# Impedance.net
KiCad netlist of a schematic drawn in EAGLE
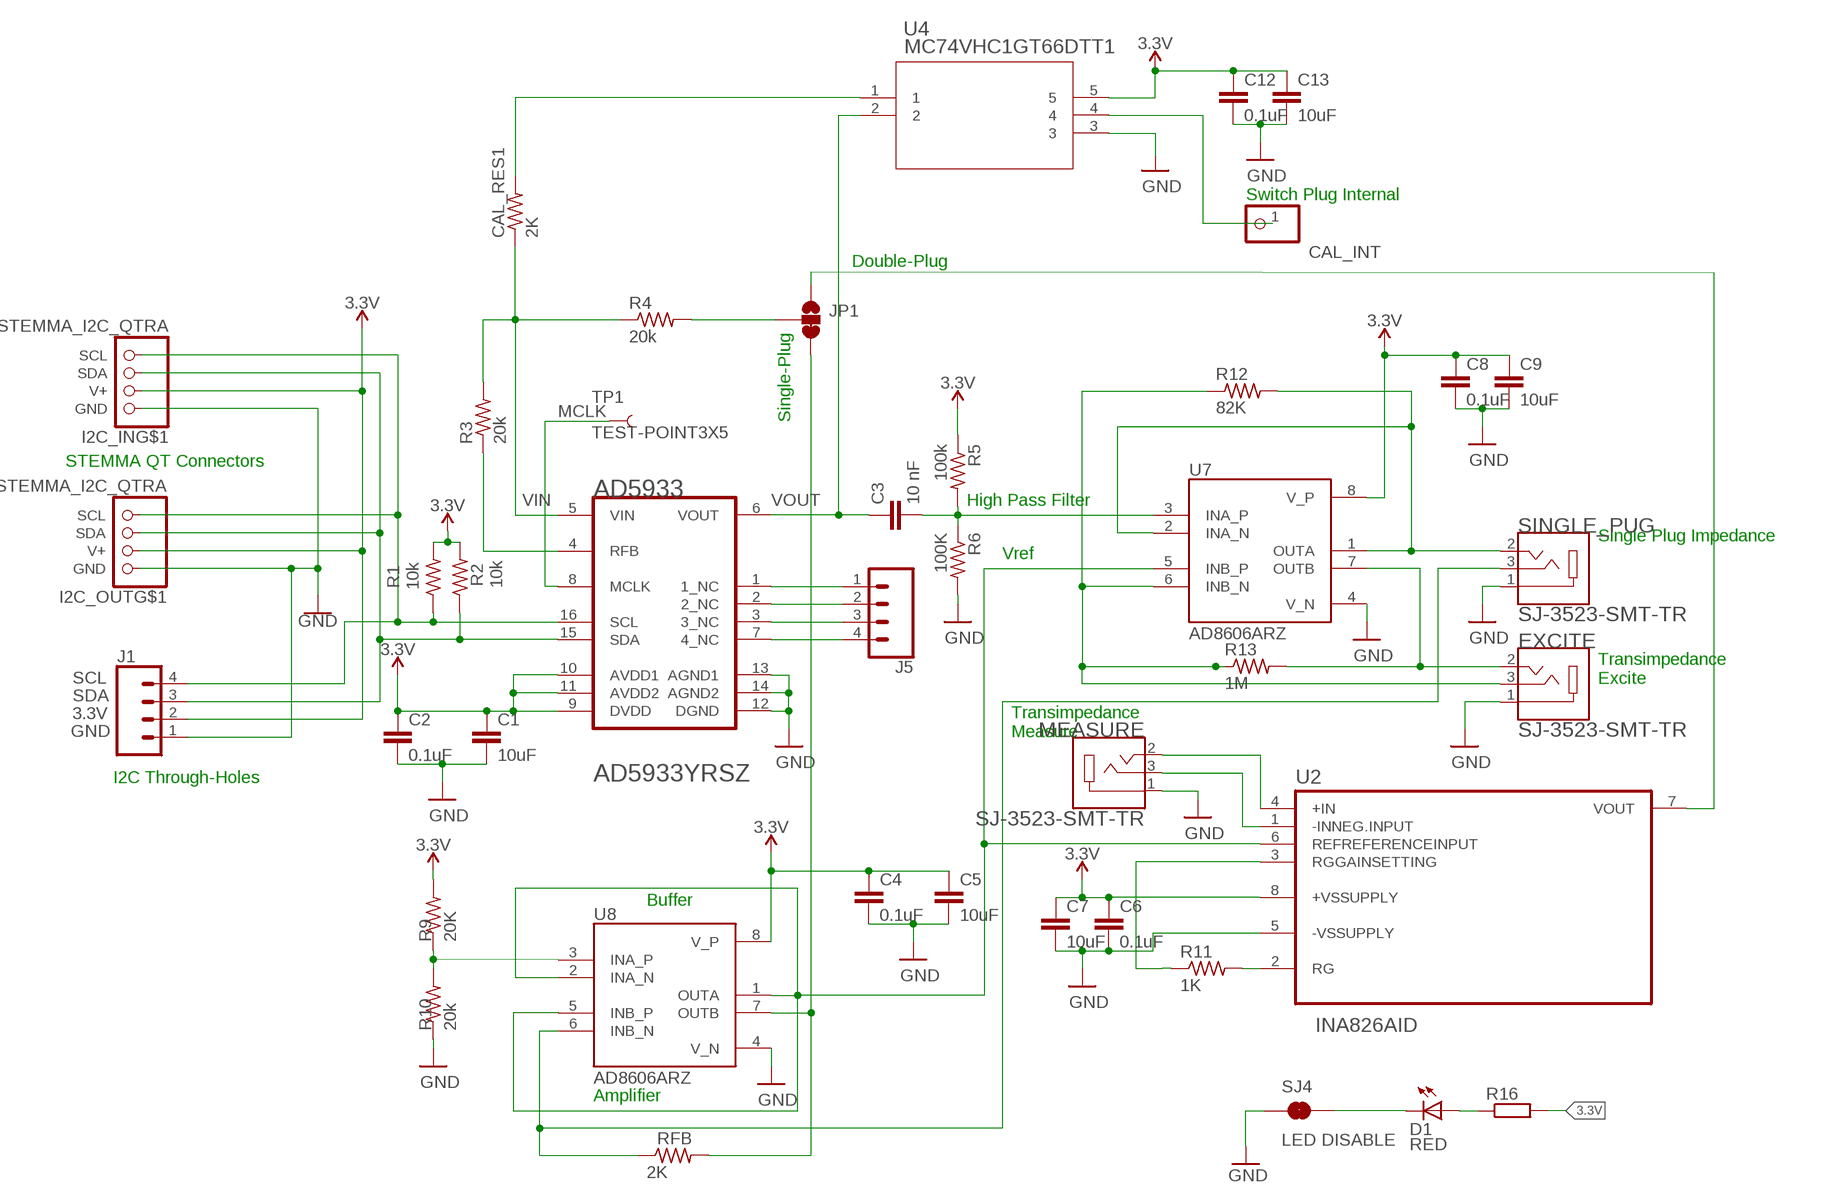
[diagram p0: schematic, sheet 1]

(export (version "E")
  (design (tool "Eeschema 10.0.6"))
  (components
    (comp (ref "AD5933")
      (value "ANALOG_DEVICES_AD5933YRSZANALOG_DEVICES_AD5933YRSZ_0_0")
      (footprint "eagle-import:ANALOG_DEVICES_AD5933YRSZ_0")
      (fields (field (name "MF") "Analog Devices") (field (name "MPN") "AD5933YRSZ"))
      (libsource (lib "eagle-import") (part "ANALOG_DEVICES_AD5933YRSZANALOG_DEVICES_AD5933YRSZ_0_0"))
    )
    (comp (ref "C1")
      (value "10uF")
      (footprint "eagle-import:C0603")
      (libsource (lib "eagle-import") (part "C-EUC0603"))
    )
    (comp (ref "C2")
      (value "0.1uF")
      (footprint "eagle-import:C0603")
      (libsource (lib "eagle-import") (part "C-EUC0603"))
    )
    (comp (ref "C3")
      (value "10 nF")
      (footprint "eagle-import:C0603")
      (libsource (lib "eagle-import") (part "C-EUC0603"))
    )
    (comp (ref "C4")
      (value "0.1uF")
      (footprint "eagle-import:C0603")
      (libsource (lib "eagle-import") (part "C-EUC0603"))
    )
    (comp (ref "C5")
      (value "10uF")
      (footprint "eagle-import:C0603")
      (libsource (lib "eagle-import") (part "C-EUC0603"))
    )
    (comp (ref "C6")
      (value "0.1uF")
      (footprint "eagle-import:C0603")
      (libsource (lib "eagle-import") (part "C-EUC0603"))
    )
    (comp (ref "C7")
      (value "10uF")
      (footprint "eagle-import:C0603")
      (libsource (lib "eagle-import") (part "C-EUC0603"))
    )
    (comp (ref "C8")
      (value "0.1uF")
      (footprint "eagle-import:C0603")
      (libsource (lib "eagle-import") (part "C-EUC0603"))
    )
    (comp (ref "C9")
      (value "10uF")
      (footprint "eagle-import:C0603")
      (libsource (lib "eagle-import") (part "C-EUC0603"))
    )
    (comp (ref "C12")
      (value "0.1uF")
      (footprint "eagle-import:C0603")
      (libsource (lib "eagle-import") (part "C-EUC0603"))
    )
    (comp (ref "C13")
      (value "10uF")
      (footprint "eagle-import:C0603")
      (libsource (lib "eagle-import") (part "C-EUC0603"))
    )
    (comp (ref "CAL_INT")
      (value "PINHD-1X1")
      (footprint "eagle-import:1X01")
      (libsource (lib "eagle-import") (part "PINHD-1X1"))
    )
    (comp (ref "CAL_RES1")
      (value "2K")
      (footprint "eagle-import:R0603")
      (libsource (lib "eagle-import") (part "R-US_R0603"))
    )
    (comp (ref "D1")
      (value "RED")
      (footprint "eagle-import:LED-0603")
      (libsource (lib "eagle-import") (part "LED-RED0603"))
    )
    (comp (ref "EXCITE")
      (value "SJ-3523-SMT-TR")
      (footprint "eagle-import:CUI_SJ-3523-SMT-TR")
      (fields (field (name "MF") "CUI Devices"))
      (libsource (lib "eagle-import") (part "SJ-3523-SMT-TR"))
    )
    (comp (ref "I2C_IN")
      (value "STEMMA_I2C_QTRA")
      (footprint "eagle-import:JST_SH4_RA")
      (libsource (lib "eagle-import") (part "STEMMA_I2C_QTRA"))
    )
    (comp (ref "I2C_OUT")
      (value "STEMMA_I2C_QTRA")
      (footprint "eagle-import:JST_SH4_RA")
      (libsource (lib "eagle-import") (part "STEMMA_I2C_QTRA"))
    )
    (comp (ref "J1")
      (value "CONN_04")
      (footprint "eagle-import:1X04")
      (libsource (lib "eagle-import") (part "CONN_04"))
    )
    (comp (ref "J5")
      (value "CONN_04")
      (footprint "eagle-import:1X04")
      (libsource (lib "eagle-import") (part "CONN_04"))
    )
    (comp (ref "JP1")
      (value "JUMPER-SMT_3_1-NC_TRACE_NO-SILK")
      (footprint "eagle-import:SMT-JUMPER_3_1-NC_TRACE_NO-SILK")
      (libsource (lib "eagle-import") (part "JUMPER-SMT_3_1-NC_TRACE_NO-SILK"))
    )
    (comp (ref "MEASURE")
      (value "SJ-3523-SMT-TR")
      (footprint "eagle-import:CUI_SJ-3523-SMT-TR")
      (fields (field (name "MF") "CUI Devices"))
      (libsource (lib "eagle-import") (part "SJ-3523-SMT-TR"))
    )
    (comp (ref "R1")
      (value "10k")
      (footprint "eagle-import:R0603")
      (libsource (lib "eagle-import") (part "R-US_R0603"))
    )
    (comp (ref "R2")
      (value "10k")
      (footprint "eagle-import:R0603")
      (libsource (lib "eagle-import") (part "R-US_R0603"))
    )
    (comp (ref "R3")
      (value "20k")
      (footprint "eagle-import:R0603")
      (libsource (lib "eagle-import") (part "R-US_R0603"))
    )
    (comp (ref "R4")
      (value "20k")
      (footprint "eagle-import:R0603")
      (libsource (lib "eagle-import") (part "R-US_R0603"))
    )
    (comp (ref "R5")
      (value "100k")
      (footprint "eagle-import:R0603")
      (libsource (lib "eagle-import") (part "R-US_R0603"))
    )
    (comp (ref "R6")
      (value "100K")
      (footprint "eagle-import:R0603")
      (libsource (lib "eagle-import") (part "R-US_R0603"))
    )
    (comp (ref "R9")
      (value "20K")
      (footprint "eagle-import:R0603")
      (libsource (lib "eagle-import") (part "R-US_R0603"))
    )
    (comp (ref "R10")
      (value "20k")
      (footprint "eagle-import:R0603")
      (libsource (lib "eagle-import") (part "R-US_R0603"))
    )
    (comp (ref "R11")
      (value "1K")
      (footprint "eagle-import:R0603")
      (libsource (lib "eagle-import") (part "R-US_R0603"))
    )
    (comp (ref "R12")
      (value "82K")
      (footprint "eagle-import:R0603")
      (libsource (lib "eagle-import") (part "R-US_R0603"))
    )
    (comp (ref "R13")
      (value "1M")
      (footprint "eagle-import:R0603")
      (libsource (lib "eagle-import") (part "R-US_R0603"))
    )
    (comp (ref "R16")
      (value "R__0603")
      (footprint "eagle-import:R0603")
      (fields (field (name "LCSC_PART") "C21190"))
      (libsource (lib "eagle-import") (part "R__06031K"))
    )
    (comp (ref "RFB")
      (value "2K")
      (footprint "eagle-import:R0603")
      (libsource (lib "eagle-import") (part "R-US_R0603"))
    )
    (comp (ref "SINGLE_PUG")
      (value "SJ-3523-SMT-TR")
      (footprint "eagle-import:CUI_SJ-3523-SMT-TR")
      (fields (field (name "MF") "CUI Devices"))
      (libsource (lib "eagle-import") (part "SJ-3523-SMT-TR"))
    )
    (comp (ref "SJ4")
      (value "LED DISABLE")
      (footprint "eagle-import:SMT-JUMPER_2_NC_TRACE_NO-SILK")
      (libsource (lib "eagle-import") (part "JUMPER-SMT_2_NC_TRACE_NO-SILK"))
    )
    (comp (ref "TP1")
      (value "TEST-POINT3X5")
      (footprint "eagle-import:PAD.03X.05")
      (libsource (lib "eagle-import") (part "TEST-POINT3X5"))
    )
    (comp (ref "U2")
      (value "INA826AID")
      (footprint "eagle-import:SOIC127P599X175-8N")
      (fields (field (name "MF") "Texas Instruments"))
      (libsource (lib "eagle-import") (part "INA826AID"))
    )
    (comp (ref "U4")
      (value "MC74VHC1GT66DTT1")
      (footprint "eagle-import:TSOP5_1P65X3P15_ONS")
      (fields (field (name "COPYRIGHT") "Copyright (C) 2024 Ultra Librarian. All rights reserved."))
      (libsource (lib "eagle-import") (part "MC74VHC1GT66DTT1"))
    )
    (comp (ref "U7")
      (value "AD8606ARZ")
      (footprint "eagle-import:SOIC127P600X175-8N")
      (fields (field (name "MF") "Analog Devices"))
      (libsource (lib "eagle-import") (part "AD8606ARZ"))
    )
    (comp (ref "U8")
      (value "AD8606ARZ")
      (footprint "eagle-import:SOIC127P600X175-8N")
      (fields (field (name "MF") "Analog Devices"))
      (libsource (lib "eagle-import") (part "AD8606ARZ"))
    )
  )
  (nets
    (net (code "1") (name "/MCLK") (class "Default")
      (node (ref "AD5933") (pin "8") (pinfunction "MCLK_8") (pintype "input"))
      (node (ref "TP1") (pin "P$1") (pinfunction "1_P$1") (pintype "bidirectional"))
    )
    (net (code "2") (name "/SCL") (class "Default")
      (node (ref "AD5933") (pin "16") (pinfunction "SCL_16") (pintype "input"))
      (node (ref "I2C_IN") (pin "4") (pinfunction "SCL_4") (pintype "passive"))
      (node (ref "I2C_OUT") (pin "4") (pinfunction "SCL_4") (pintype "passive"))
      (node (ref "J1") (pin "4") (pinfunction "4_4") (pintype "passive"))
      (node (ref "R1") (pin "1") (pinfunction "1_1") (pintype "passive"))
    )
    (net (code "3") (name "/SDA") (class "Default")
      (node (ref "AD5933") (pin "15") (pinfunction "SDA_15") (pintype "bidirectional"))
      (node (ref "I2C_IN") (pin "3") (pinfunction "SDA_3") (pintype "passive"))
      (node (ref "I2C_OUT") (pin "3") (pinfunction "SDA_3") (pintype "passive"))
      (node (ref "J1") (pin "3") (pinfunction "3_3") (pintype "passive"))
      (node (ref "R2") (pin "1") (pinfunction "1_1") (pintype "passive"))
    )
    (net (code "4") (name "/VIN") (class "Default")
      (node (ref "AD5933") (pin "5") (pinfunction "VIN_5") (pintype "input"))
      (node (ref "CAL_RES1") (pin "1") (pinfunction "1_1") (pintype "passive"))
      (node (ref "R3") (pin "2") (pinfunction "2_2") (pintype "passive"))
      (node (ref "R4") (pin "1") (pinfunction "1_1") (pintype "passive"))
    )
    (net (code "5") (name "/VOUT") (class "Default")
      (node (ref "AD5933") (pin "6") (pinfunction "VOUT_6") (pintype "output"))
      (node (ref "C3") (pin "1") (pinfunction "1_1") (pintype "passive"))
      (node (ref "U4") (pin "2") (pinfunction "2_2") (pintype "passive"))
    )
    (net (code "6") (name "3.3V") (class "Default")
      (node (ref "AD5933") (pin "10") (pinfunction "AVDD1_10") (pintype "power_in"))
      (node (ref "AD5933") (pin "11") (pinfunction "AVDD2_11") (pintype "power_in"))
      (node (ref "AD5933") (pin "9") (pinfunction "DVDD_9") (pintype "power_in"))
      (node (ref "C1") (pin "1") (pinfunction "1_1") (pintype "passive"))
      (node (ref "C12") (pin "1") (pinfunction "1_1") (pintype "passive"))
      (node (ref "C13") (pin "1") (pinfunction "1_1") (pintype "passive"))
      (node (ref "C2") (pin "1") (pinfunction "1_1") (pintype "passive"))
      (node (ref "C4") (pin "1") (pinfunction "1_1") (pintype "passive"))
      (node (ref "C5") (pin "1") (pinfunction "1_1") (pintype "passive"))
      (node (ref "C6") (pin "1") (pinfunction "1_1") (pintype "passive"))
      (node (ref "C7") (pin "1") (pinfunction "1_1") (pintype "passive"))
      (node (ref "C8") (pin "1") (pinfunction "1_1") (pintype "passive"))
      (node (ref "C9") (pin "1") (pinfunction "1_1") (pintype "passive"))
      (node (ref "I2C_IN") (pin "2") (pinfunction "V+_2") (pintype "passive"))
      (node (ref "I2C_OUT") (pin "2") (pinfunction "V+_2") (pintype "passive"))
      (node (ref "J1") (pin "2") (pinfunction "2_2") (pintype "passive"))
      (node (ref "R1") (pin "2") (pinfunction "2_2") (pintype "passive"))
      (node (ref "R16") (pin "2") (pinfunction "2_2") (pintype "passive"))
      (node (ref "R2") (pin "2") (pinfunction "2_2") (pintype "passive"))
      (node (ref "R5") (pin "1") (pinfunction "1_1") (pintype "passive"))
      (node (ref "R9") (pin "2") (pinfunction "2_2") (pintype "passive"))
      (node (ref "U2") (pin "8") (pinfunction "+VSSUPPLY_8") (pintype "bidirectional"))
      (node (ref "U4") (pin "5") (pinfunction "5_5") (pintype "passive"))
      (node (ref "U7") (pin "8") (pinfunction "V_P_8") (pintype "power_in"))
      (node (ref "U8") (pin "8") (pinfunction "V_P_8") (pintype "power_in"))
    )
    (net (code "7") (name "GND") (class "Default")
      (node (ref "AD5933") (pin "12") (pinfunction "DGND_12") (pintype "power_in"))
      (node (ref "AD5933") (pin "13") (pinfunction "AGND1_13") (pintype "power_in"))
      (node (ref "AD5933") (pin "14") (pinfunction "AGND2_14") (pintype "power_in"))
      (node (ref "C1") (pin "2") (pinfunction "2_2") (pintype "passive"))
      (node (ref "C12") (pin "2") (pinfunction "2_2") (pintype "passive"))
      (node (ref "C13") (pin "2") (pinfunction "2_2") (pintype "passive"))
      (node (ref "C2") (pin "2") (pinfunction "2_2") (pintype "passive"))
      (node (ref "C4") (pin "2") (pinfunction "2_2") (pintype "passive"))
      (node (ref "C5") (pin "2") (pinfunction "2_2") (pintype "passive"))
      (node (ref "C6") (pin "2") (pinfunction "2_2") (pintype "passive"))
      (node (ref "C7") (pin "2") (pinfunction "2_2") (pintype "passive"))
      (node (ref "C8") (pin "2") (pinfunction "2_2") (pintype "passive"))
      (node (ref "C9") (pin "2") (pinfunction "2_2") (pintype "passive"))
      (node (ref "EXCITE") (pin "1") (pinfunction "1_1") (pintype "passive"))
      (node (ref "I2C_IN") (pin "1") (pinfunction "GND_1") (pintype "passive"))
      (node (ref "I2C_OUT") (pin "1") (pinfunction "GND_1") (pintype "passive"))
      (node (ref "J1") (pin "1") (pinfunction "1_1") (pintype "passive"))
      (node (ref "MEASURE") (pin "1") (pinfunction "1_1") (pintype "passive"))
      (node (ref "R10") (pin "1") (pinfunction "1_1") (pintype "passive"))
      (node (ref "R6") (pin "2") (pinfunction "2_2") (pintype "passive"))
      (node (ref "SINGLE_PUG") (pin "1") (pinfunction "1_1") (pintype "passive"))
      (node (ref "SJ4") (pin "1") (pinfunction "1_1") (pintype "passive"))
      (node (ref "U2") (pin "5") (pinfunction "-VSSUPPLY_5") (pintype "bidirectional"))
      (node (ref "U4") (pin "3") (pinfunction "3_3") (pintype "passive"))
      (node (ref "U7") (pin "4") (pinfunction "V_N_4") (pintype "power_in"))
      (node (ref "U8") (pin "4") (pinfunction "V_N_4") (pintype "power_in"))
    )
    (net (code "8") (name "Net-(AD5933-1_NC)") (class "Default")
      (node (ref "AD5933") (pin "1") (pinfunction "1_NC_1") (pintype "passive"))
      (node (ref "J5") (pin "1") (pinfunction "1_1") (pintype "passive"))
    )
    (net (code "9") (name "Net-(AD5933-2_NC)") (class "Default")
      (node (ref "AD5933") (pin "2") (pinfunction "2_NC_2") (pintype "passive"))
      (node (ref "J5") (pin "2") (pinfunction "2_2") (pintype "passive"))
    )
    (net (code "10") (name "Net-(AD5933-3_NC)") (class "Default")
      (node (ref "AD5933") (pin "3") (pinfunction "3_NC_3") (pintype "passive"))
      (node (ref "J5") (pin "3") (pinfunction "3_3") (pintype "passive"))
    )
    (net (code "11") (name "Net-(AD5933-4_NC)") (class "Default")
      (node (ref "AD5933") (pin "7") (pinfunction "4_NC_7") (pintype "passive"))
      (node (ref "J5") (pin "4") (pinfunction "4_4") (pintype "passive"))
    )
    (net (code "12") (name "Net-(AD5933-RFB)") (class "Default")
      (node (ref "AD5933") (pin "4") (pinfunction "RFB_4") (pintype "input"))
      (node (ref "R3") (pin "1") (pinfunction "1_1") (pintype "passive"))
    )
    (net (code "13") (name "Net-(CAL_INT-Pad1)") (class "Default")
      (node (ref "CAL_INT") (pin "1") (pinfunction "1_1") (pintype "passive"))
      (node (ref "U4") (pin "4") (pinfunction "4_4") (pintype "passive"))
    )
    (net (code "14") (name "Net-(CAL_RES1-Pad2)") (class "Default")
      (node (ref "CAL_RES1") (pin "2") (pinfunction "2_2") (pintype "passive"))
      (node (ref "U4") (pin "1") (pinfunction "1_1") (pintype "passive"))
    )
    (net (code "15") (name "Net-(D1-PadA)") (class "Default")
      (node (ref "D1") (pin "A") (pinfunction "A_A") (pintype "passive"))
      (node (ref "R16") (pin "1") (pinfunction "1_1") (pintype "passive"))
    )
    (net (code "16") (name "Net-(D1-PadC)") (class "Default")
      (node (ref "D1") (pin "C") (pinfunction "C_C") (pintype "passive"))
      (node (ref "SJ4") (pin "2") (pinfunction "2_2") (pintype "passive"))
    )
    (net (code "17") (name "Net-(JP1-Pad2)") (class "Default")
      (node (ref "JP1") (pin "2") (pinfunction "2_2") (pintype "passive"))
      (node (ref "R4") (pin "2") (pinfunction "2_2") (pintype "passive"))
    )
    (net (code "18") (name "Net-(U2-+IN)") (class "Default")
      (node (ref "MEASURE") (pin "2") (pinfunction "2_2") (pintype "passive"))
      (node (ref "U2") (pin "4") (pinfunction "+IN_4") (pintype "input"))
    )
    (net (code "19") (name "Net-(U2--INNEG.INPUT)") (class "Default")
      (node (ref "MEASURE") (pin "3") (pinfunction "3_3") (pintype "passive"))
      (node (ref "U2") (pin "1") (pinfunction "-INNEG.INPUT_1") (pintype "input"))
    )
    (net (code "20") (name "Net-(U2-REFREFERENCEINPUT)") (class "Default")
      (node (ref "U2") (pin "6") (pinfunction "REFREFERENCEINPUT_6") (pintype "input"))
      (node (ref "U7") (pin "5") (pinfunction "INB_P_5") (pintype "input"))
      (node (ref "U8") (pin "1") (pinfunction "OUTA_1") (pintype "input"))
      (node (ref "U8") (pin "2") (pinfunction "INA_N_2") (pintype "input"))
      (node (ref "U8") (pin "5") (pinfunction "INB_P_5") (pintype "input"))
    )
    (net (code "21") (name "Net-(U2-RG)") (class "Default")
      (node (ref "R11") (pin "2") (pinfunction "2_2") (pintype "passive"))
      (node (ref "U2") (pin "2") (pinfunction "RG_2") (pintype "bidirectional"))
    )
    (net (code "22") (name "Net-(U2-RGGAINSETTING)") (class "Default")
      (node (ref "R11") (pin "1") (pinfunction "1_1") (pintype "passive"))
      (node (ref "U2") (pin "3") (pinfunction "RGGAINSETTING_3") (pintype "input"))
    )
    (net (code "23") (name "Net-(U2-VOUT)") (class "Default")
      (node (ref "JP1") (pin "1") (pinfunction "1_1") (pintype "passive"))
      (node (ref "U2") (pin "7") (pinfunction "VOUT_7") (pintype "output"))
    )
    (net (code "24") (name "Net-(U7-INA_N)") (class "Default")
      (node (ref "R12") (pin "2") (pinfunction "2_2") (pintype "passive"))
      (node (ref "SINGLE_PUG") (pin "2") (pinfunction "2_2") (pintype "passive"))
      (node (ref "U7") (pin "1") (pinfunction "OUTA_1") (pintype "input"))
      (node (ref "U7") (pin "2") (pinfunction "INA_N_2") (pintype "input"))
    )
    (net (code "25") (name "Net-(U7-INA_P)") (class "Default")
      (node (ref "C3") (pin "2") (pinfunction "2_2") (pintype "passive"))
      (node (ref "R5") (pin "2") (pinfunction "2_2") (pintype "passive"))
      (node (ref "R6") (pin "1") (pinfunction "1_1") (pintype "passive"))
      (node (ref "U7") (pin "3") (pinfunction "INA_P_3") (pintype "input"))
    )
    (net (code "26") (name "Net-(U7-INB_N)") (class "Default")
      (node (ref "EXCITE") (pin "3") (pinfunction "3_3") (pintype "passive"))
      (node (ref "R12") (pin "1") (pinfunction "1_1") (pintype "passive"))
      (node (ref "R13") (pin "1") (pinfunction "1_1") (pintype "passive"))
      (node (ref "U7") (pin "6") (pinfunction "INB_N_6") (pintype "input"))
    )
    (net (code "27") (name "Net-(U7-OUTB)") (class "Default")
      (node (ref "EXCITE") (pin "2") (pinfunction "2_2") (pintype "passive"))
      (node (ref "R13") (pin "2") (pinfunction "2_2") (pintype "passive"))
      (node (ref "U7") (pin "7") (pinfunction "OUTB_7") (pintype "input"))
    )
    (net (code "28") (name "Net-(U8-INA_P)") (class "Default")
      (node (ref "R10") (pin "2") (pinfunction "2_2") (pintype "passive"))
      (node (ref "R9") (pin "1") (pinfunction "1_1") (pintype "passive"))
      (node (ref "U8") (pin "3") (pinfunction "INA_P_3") (pintype "input"))
    )
    (net (code "29") (name "Net-(U8-INB_N)") (class "Default")
      (node (ref "RFB") (pin "1") (pinfunction "1_1") (pintype "passive"))
      (node (ref "SINGLE_PUG") (pin "3") (pinfunction "3_3") (pintype "passive"))
      (node (ref "U8") (pin "6") (pinfunction "INB_N_6") (pintype "input"))
    )
    (net (code "30") (name "Net-(U8-OUTB)") (class "Default")
      (node (ref "RFB") (pin "2") (pinfunction "2_2") (pintype "passive"))
      (node (ref "U8") (pin "7") (pinfunction "OUTB_7") (pintype "input"))
    )
    (net (code "31") (name "unconnected-(JP1-Pad3)") (class "Default")
      (node (ref "JP1") (pin "3") (pinfunction "3_3") (pintype "passive"))
    )
  )
)
